# RFDesign.net
KiCad netlist of a schematic drawn in Altium Designer
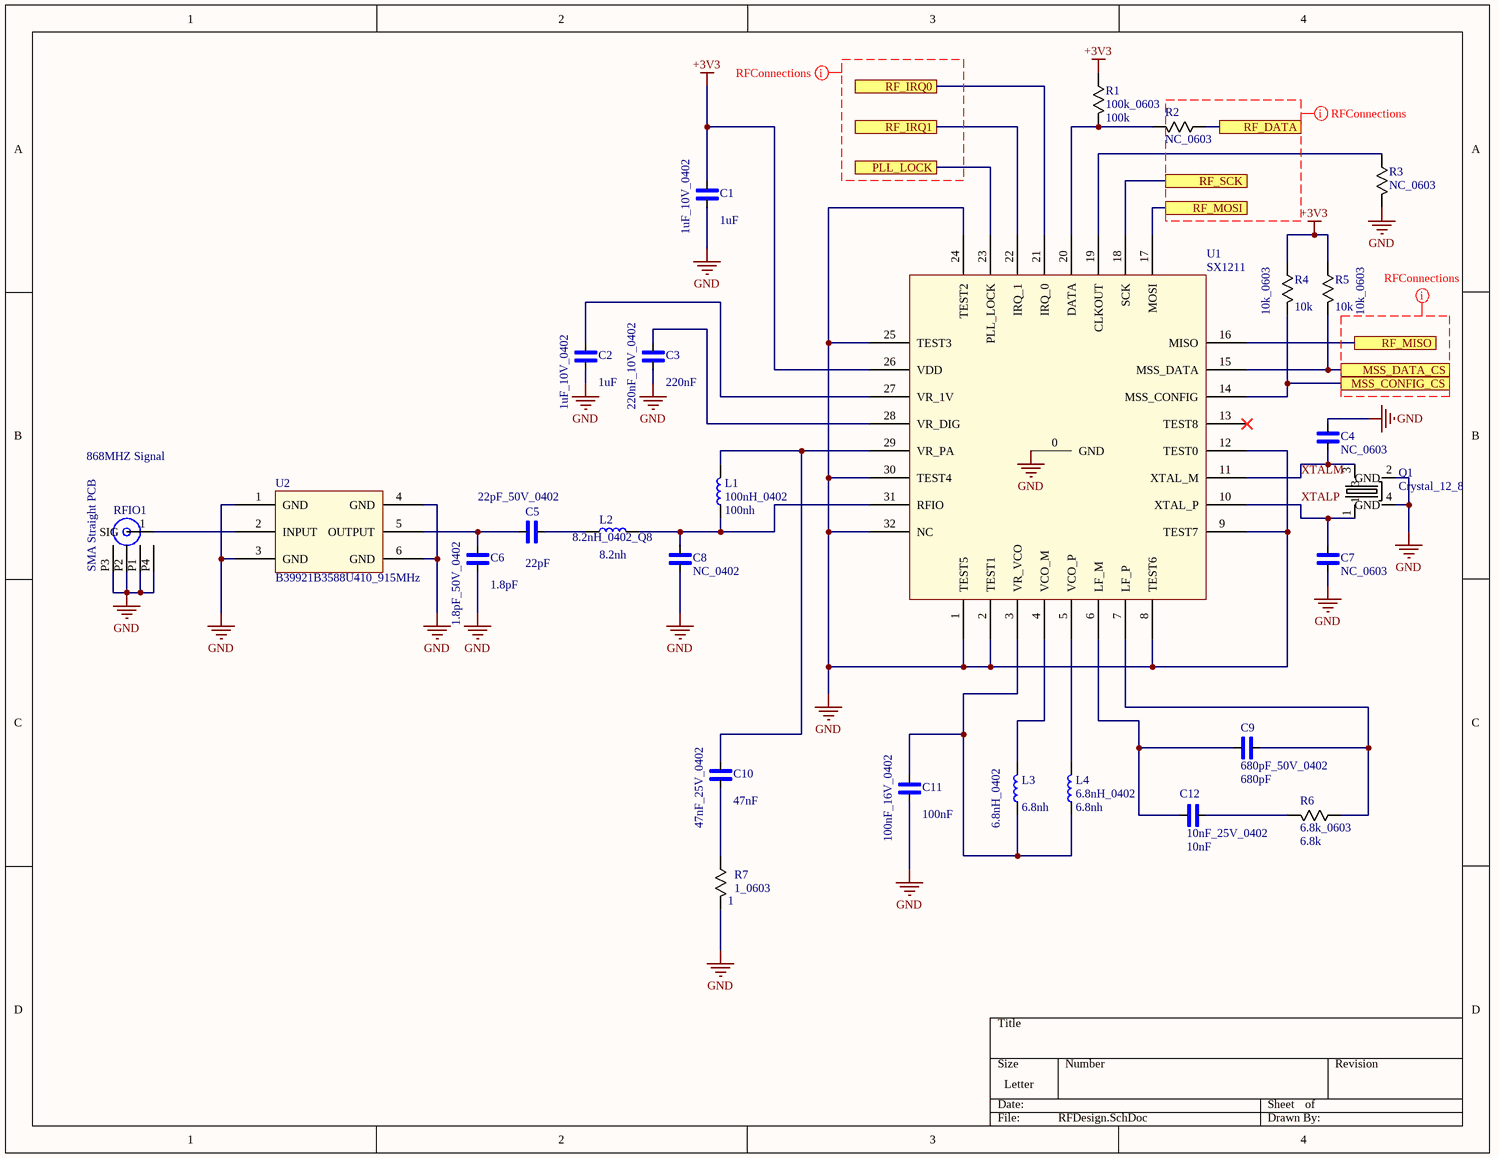
[diagram p0: RFDesign.SchDoc]

(export (version "E")
  (design (tool "Eeschema 10.0.6"))
  (components
    (comp (ref "C1")
      (value "1uF_10V_0402")
      (footprint "0402")
      (fields
        (field (name "MANUFACTURER") "Murata")
        (field (name "MANUFACTURER PART NUMBER") "GRM155R61A105KE15D")
        (field (name "TOLERANCE") "20%")
        (field (name "CAPACITANCE") "1uF")
      )
      (libsource (lib "Capacitors") (part "1uF_10V_0402"))
    )
    (comp (ref "C2")
      (value "1uF_10V_0402")
      (footprint "0402")
      (fields
        (field (name "MANUFACTURER") "Murata")
        (field (name "MANUFACTURER PART NUMBER") "GRM155R61A105KE15D")
        (field (name "TOLERANCE") "20%")
        (field (name "CAPACITANCE") "1uF")
      )
      (libsource (lib "Capacitors") (part "1uF_10V_0402"))
    )
    (comp (ref "C3")
      (value "220nF_10V_0402")
      (footprint "0402")
      (fields
        (field (name "MANUFACTURER") "Murata")
        (field (name "MANUFACTURER PART NUMBER") "GRM155R61A224KE19J")
        (field (name "TOLERANCE") "10%")
        (field (name "CAPACITANCE") "220nF")
      )
      (libsource (lib "Capacitors") (part "220nF_10V_0402"))
    )
    (comp (ref "C4") (value "NC_0603") (footprint "0603") (libsource (lib "Capacitors") (part "NC_0603")))
    (comp (ref "C5")
      (value "22pF_50V_0402")
      (footprint "0402")
      (fields
        (field (name "MANUFACTURER") "Murata")
        (field (name "MANUFACTURER PART NUMBER") "GRM1555C1H220JA01D")
        (field (name "TOLERANCE") "5%")
        (field (name "CAPACITANCE") "22pF")
      )
      (libsource (lib "Capacitors") (part "22pF_50V_0402"))
    )
    (comp (ref "C6")
      (value "1.8pF_50V_0402")
      (footprint "0402")
      (fields
        (field (name "MANUFACTURER") "Murata")
        (field (name "MANUFACTURER PART NUMBER") "GRM1555C1H1R8CA01D")
        (field (name "VOLTAGE") "50V")
        (field (name "CAPACITANCE") "1.8pF")
      )
      (libsource (lib "Capacitors") (part "1.8pF_50V_0402"))
    )
    (comp (ref "C7") (value "NC_0603") (footprint "0603") (libsource (lib "Capacitors") (part "NC_0603")))
    (comp (ref "C8") (value "NC_0402") (footprint "0402") (libsource (lib "Capacitors") (part "NC_0402")))
    (comp (ref "C9")
      (value "680pF_50V_0402")
      (footprint "0402")
      (fields
        (field (name "MANUFACTURER") "Murata")
        (field (name "MANUFACTURER PART NUMBER") "GRM1555C1H681JA01D")
        (field (name "TOLERANCE") "5%")
        (field (name "CAPACITANCE") "680pF")
      )
      (libsource (lib "Capacitors") (part "680pF_50V_0402"))
    )
    (comp (ref "C10")
      (value "47nF_25V_0402")
      (footprint "0402")
      (fields
        (field (name "MANUFACTURER") "Murata")
        (field (name "MANUFACTURER PART NUMBER") "GRM155R71E473KA88J")
        (field (name "TOLERANCE") "10%")
        (field (name "CAPACITANCE") "47nF")
      )
      (libsource (lib "Capacitors") (part "47nF_25V_0402"))
    )
    (comp (ref "C11")
      (value "100nF_16V_0402")
      (footprint "0402")
      (fields
        (field (name "MANUFACTURER") "Murata")
        (field (name "MANUFACTURER PART NUMBER") "GRM155-R7-1C-104K-A88-D")
        (field (name "TOLERANCE") "10%")
        (field (name "CAPACITANCE") "100nF")
      )
      (libsource (lib "Capacitors") (part "100nF_16V_0402"))
    )
    (comp (ref "C12")
      (value "10nF_25V_0402")
      (footprint "0402")
      (fields
        (field (name "MANUFACTURER") "Murata")
        (field (name "MANUFACTURER PART NUMBER") "GRM155R71E103KA01D")
        (field (name "TOLERANCE") "10%")
        (field (name "CAPACITANCE") "10nF")
      )
      (libsource (lib "Capacitors") (part "10nF_25V_0402"))
    )
    (comp (ref "L1")
      (value "100nH_0402")
      (footprint "0402")
      (fields
        (field (name "MANUFACTURER") "Murata")
        (field (name "MANUFACTURER PART NUMBER") "LQW15ANR10J00D")
        (field (name "TOLERANCE") "5%")
        (field (name "INDUCTANCE") "100nh")
      )
      (libsource (lib "Inductors") (part "100nH_0402"))
    )
    (comp (ref "L2")
      (value "8.2nH_0402_Q8")
      (footprint "0402")
      (fields
        (field (name "MANUFACTURER") "Murata")
        (field (name "MANUFACTURER PART NUMBER") "LQG15HS8N2J02D")
        (field (name "TOLERANCE") "5%")
        (field (name "INDUCTANCE") "8.2nh")
      )
      (libsource (lib "Inductors") (part "8.2nH_0402_Q8"))
    )
    (comp (ref "L3")
      (value "6.8nH_0402")
      (footprint "0402")
      (fields
        (field (name "MANUFACTURER") "Murata")
        (field (name "MANUFACTURER PART NUMBER") "LQW15AN6N8H00D")
        (field (name "TOLERANCE") "3%")
        (field (name "INDUCTANCE") "6.8nh")
      )
      (libsource (lib "Inductors") (part "6.8nH_0402"))
    )
    (comp (ref "L4")
      (value "6.8nH_0402")
      (footprint "0402")
      (fields
        (field (name "MANUFACTURER") "Murata")
        (field (name "MANUFACTURER PART NUMBER") "LQW15AN6N8H00D")
        (field (name "TOLERANCE") "3%")
        (field (name "INDUCTANCE") "6.8nh")
      )
      (libsource (lib "Inductors") (part "6.8nH_0402"))
    )
    (comp (ref "Q1")
      (value "Crystal_12_8")
      (footprint "4-SMD No Lead")
      (description "CRYSTAL 12.8000MHZ 10PF SMD")
      (fields (field (name "PART NO") "ABM3B-12.800MHZ-10-1-U-T"))
      (libsource (lib "Crystals") (part "Crystal_12_8"))
    )
    (comp (ref "R1")
      (value "100k_0603")
      (footprint "0603")
      (fields
        (field (name "MANUFACTURER") "Vishay")
        (field (name "MANUFACTURER PART NUMBER") "CRCW0603100KFKEA")
        (field (name "TOLERANCE") "1%")
        (field (name "RESISTANCE") "100k")
      )
      (libsource (lib "Resistors") (part "100k_0603"))
    )
    (comp (ref "R2") (value "NC_0603") (footprint "0603") (libsource (lib "Resistors") (part "NC_0603")))
    (comp (ref "R3") (value "NC_0603") (footprint "0603") (libsource (lib "Resistors") (part "NC_0603")))
    (comp (ref "R4")
      (value "10k_0603")
      (footprint "0603")
      (fields
        (field (name "MANUFACTURER") "Panasonic")
        (field (name "MANUFACTURER PART NUMBER") "ERJ-3EKF1002V")
        (field (name "TOLERANCE") "1%")
        (field (name "RESISTANCE") "10k")
      )
      (libsource (lib "Resistors") (part "10k_0603"))
    )
    (comp (ref "R5")
      (value "10k_0603")
      (footprint "0603")
      (fields
        (field (name "MANUFACTURER") "Panasonic")
        (field (name "MANUFACTURER PART NUMBER") "ERJ-3EKF1002V")
        (field (name "TOLERANCE") "1%")
        (field (name "RESISTANCE") "10k")
      )
      (libsource (lib "Resistors") (part "10k_0603"))
    )
    (comp (ref "R6")
      (value "6.8k_0603")
      (footprint "0603")
      (fields
        (field (name "MANUFACTURER") "Vishay")
        (field (name "MANUFACTURER PART NUMBER") "CRCW06036K80FKEA")
        (field (name "TOLERANCE") "1%")
        (field (name "RESISTANCE") "6.8k")
      )
      (libsource (lib "Resistors") (part "6.8k_0603"))
    )
    (comp (ref "R7")
      (value "1_0603")
      (footprint "0603")
      (fields
        (field (name "MANUFACTURER") "Vishay Dale")
        (field (name "MANUFACTURER PART NUMBER") "CRCW06031R00FKEA")
        (field (name "TOLERANCE") "1%")
        (field (name "RESISTANCE") "1")
      )
      (libsource (lib "Resistors") (part "1_0603"))
    )
    (comp (ref "RFIO1")
      (value "SMA Straight PCB")
      (footprint "SMA Straight PCB")
      (description "RF Connector SMA Straight PCB Jack Surface Mount 50 Ohm")
      (fields (field (name "PART NO") "132134-15"))
      (libsource (lib "Connectors") (part "SMA Straight PCB"))
    )
    (comp (ref "U1")
      (value "SX1211")
      (footprint "SX1211")
      (description "SX1211I084")
      (libsource (lib "RFICs") (part "SX1211"))
    )
    (comp (ref "U2")
      (value "B39921B3588U410_915MHz")
      (footprint "B39871B3715U410")
      (libsource (lib "Filters") (part "B39921B3588U410_915MHz"))
    )
  )
  (nets
    (net (code "1") (name "+3V3") (class "Default")
      (node (ref "C1") (pin "2") (pinfunction "2_2") (pintype "passive"))
      (node (ref "R1") (pin "2") (pinfunction "2_2") (pintype "passive"))
      (node (ref "R4") (pin "2") (pinfunction "2_2") (pintype "passive"))
      (node (ref "R5") (pin "2") (pinfunction "2_2") (pintype "passive"))
      (node (ref "U1") (pin "26") (pinfunction "VDD_26") (pintype "passive"))
    )
    (net (code "2") (name "/MSS_CONFIG_CS") (class "Default")
      (node (ref "R4") (pin "1") (pinfunction "1_1") (pintype "passive"))
      (node (ref "U1") (pin "14") (pinfunction "MSS_CONFIG_14") (pintype "passive"))
    )
    (net (code "3") (name "/MSS_DATA_CS") (class "Default")
      (node (ref "R5") (pin "1") (pinfunction "1_1") (pintype "passive"))
      (node (ref "U1") (pin "15") (pinfunction "MSS_DATA_15") (pintype "passive"))
    )
    (net (code "4") (name "/PLL_LOCK") (class "Default")
      (node (ref "U1") (pin "23") (pinfunction "PLL_LOCK_23") (pintype "passive"))
    )
    (net (code "5") (name "/RF_DATA") (class "Default")
      (node (ref "R2") (pin "2") (pinfunction "2_2") (pintype "passive"))
    )
    (net (code "6") (name "/RF_IRQ0") (class "Default")
      (node (ref "U1") (pin "21") (pinfunction "IRQ_0_21") (pintype "passive"))
    )
    (net (code "7") (name "/RF_IRQ1") (class "Default")
      (node (ref "U1") (pin "22") (pinfunction "IRQ_1_22") (pintype "passive"))
    )
    (net (code "8") (name "/RF_MISO") (class "Default")
      (node (ref "U1") (pin "16") (pinfunction "MISO_16") (pintype "passive"))
    )
    (net (code "9") (name "/RF_MOSI") (class "Default")
      (node (ref "U1") (pin "17") (pinfunction "MOSI_17") (pintype "passive"))
    )
    (net (code "10") (name "/RF_SCK") (class "Default")
      (node (ref "U1") (pin "18") (pinfunction "SCK_18") (pintype "passive"))
    )
    (net (code "11") (name "/XTALM") (class "Default")
      (node (ref "C4") (pin "1") (pinfunction "1_1") (pintype "passive"))
      (node (ref "Q1") (pin "3") (pinfunction "3_3") (pintype "passive"))
      (node (ref "U1") (pin "11") (pinfunction "XTAL_M_11") (pintype "passive"))
    )
    (net (code "12") (name "/XTALP") (class "Default")
      (node (ref "C7") (pin "2") (pinfunction "2_2") (pintype "passive"))
      (node (ref "Q1") (pin "1") (pinfunction "1_1") (pintype "passive"))
      (node (ref "U1") (pin "10") (pinfunction "XTAL_P_10") (pintype "passive"))
    )
    (net (code "13") (name "GND") (class "Default")
      (node (ref "C1") (pin "1") (pinfunction "1_1") (pintype "passive"))
      (node (ref "C11") (pin "1") (pinfunction "1_1") (pintype "passive"))
      (node (ref "C2") (pin "1") (pinfunction "1_1") (pintype "passive"))
      (node (ref "C3") (pin "1") (pinfunction "1_1") (pintype "passive"))
      (node (ref "C4") (pin "2") (pinfunction "2_2") (pintype "passive"))
      (node (ref "C6") (pin "1") (pinfunction "1_1") (pintype "passive"))
      (node (ref "C7") (pin "1") (pinfunction "1_1") (pintype "passive"))
      (node (ref "C8") (pin "1") (pinfunction "1_1") (pintype "passive"))
      (node (ref "Q1") (pin "2") (pinfunction "GND_2") (pintype "passive"))
      (node (ref "Q1") (pin "4") (pinfunction "GND_4") (pintype "passive"))
      (node (ref "R3") (pin "1") (pinfunction "1_1") (pintype "passive"))
      (node (ref "R7") (pin "1") (pinfunction "1_1") (pintype "passive"))
      (node (ref "RFIO1") (pin "P1") (pintype "passive"))
      (node (ref "RFIO1") (pin "P2") (pintype "passive"))
      (node (ref "RFIO1") (pin "P3") (pintype "passive"))
      (node (ref "RFIO1") (pin "P4") (pintype "passive"))
      (node (ref "U1") (pin "0") (pinfunction "GND_0") (pintype "passive"))
      (node (ref "U1") (pin "1") (pinfunction "TEST5_1") (pintype "passive"))
      (node (ref "U1") (pin "12") (pinfunction "TEST0_12") (pintype "passive"))
      (node (ref "U1") (pin "2") (pinfunction "TEST1_2") (pintype "passive"))
      (node (ref "U1") (pin "24") (pinfunction "TEST2_24") (pintype "passive"))
      (node (ref "U1") (pin "25") (pinfunction "TEST3_25") (pintype "passive"))
      (node (ref "U1") (pin "30") (pinfunction "TEST4_30") (pintype "passive"))
      (node (ref "U1") (pin "32") (pinfunction "NC_32") (pintype "passive"))
      (node (ref "U1") (pin "8") (pinfunction "TEST6_8") (pintype "passive"))
      (node (ref "U1") (pin "9") (pinfunction "TEST7_9") (pintype "passive"))
      (node (ref "U2") (pin "1") (pinfunction "GND_1") (pintype "passive"))
      (node (ref "U2") (pin "3") (pinfunction "GND_3") (pintype "passive"))
      (node (ref "U2") (pin "4") (pinfunction "GND_4") (pintype "passive"))
      (node (ref "U2") (pin "6") (pinfunction "GND_6") (pintype "passive"))
    )
    (net (code "14") (name "Net-(C5-Pad2)") (class "Default")
      (node (ref "C5") (pin "2") (pinfunction "2_2") (pintype "passive"))
      (node (ref "L2") (pin "1") (pinfunction "1_1") (pintype "passive"))
    )
    (net (code "15") (name "Net-(C10-Pad1)") (class "Default")
      (node (ref "C10") (pin "1") (pinfunction "1_1") (pintype "passive"))
      (node (ref "R7") (pin "2") (pinfunction "2_2") (pintype "passive"))
    )
    (net (code "16") (name "Net-(C12-Pad2)") (class "Default")
      (node (ref "C12") (pin "2") (pinfunction "2_2") (pintype "passive"))
      (node (ref "R6") (pin "1") (pinfunction "1_1") (pintype "passive"))
    )
    (net (code "17") (name "Net-(RFIO1-SIG)") (class "Default")
      (node (ref "RFIO1") (pin "1") (pinfunction "SIG_1") (pintype "passive"))
      (node (ref "U2") (pin "2") (pinfunction "INPUT_2") (pintype "passive"))
    )
    (net (code "18") (name "Net-(U1-CLKOUT)") (class "Default")
      (node (ref "R3") (pin "2") (pinfunction "2_2") (pintype "passive"))
      (node (ref "U1") (pin "19") (pinfunction "CLKOUT_19") (pintype "passive"))
    )
    (net (code "19") (name "Net-(U1-DATA)") (class "Default")
      (node (ref "R1") (pin "1") (pinfunction "1_1") (pintype "passive"))
      (node (ref "R2") (pin "1") (pinfunction "1_1") (pintype "passive"))
      (node (ref "U1") (pin "20") (pinfunction "DATA_20") (pintype "passive"))
    )
    (net (code "20") (name "Net-(U1-LF_M)") (class "Default")
      (node (ref "C12") (pin "1") (pinfunction "1_1") (pintype "passive"))
      (node (ref "C9") (pin "1") (pinfunction "1_1") (pintype "passive"))
      (node (ref "U1") (pin "6") (pinfunction "LF_M_6") (pintype "passive"))
    )
    (net (code "21") (name "Net-(U1-LF_P)") (class "Default")
      (node (ref "C9") (pin "2") (pinfunction "2_2") (pintype "passive"))
      (node (ref "R6") (pin "2") (pinfunction "2_2") (pintype "passive"))
      (node (ref "U1") (pin "7") (pinfunction "LF_P_7") (pintype "passive"))
    )
    (net (code "22") (name "Net-(U1-RFIO)") (class "Default")
      (node (ref "C8") (pin "2") (pinfunction "2_2") (pintype "passive"))
      (node (ref "L1") (pin "1") (pinfunction "1_1") (pintype "passive"))
      (node (ref "L2") (pin "2") (pinfunction "2_2") (pintype "passive"))
      (node (ref "U1") (pin "31") (pinfunction "RFIO_31") (pintype "passive"))
    )
    (net (code "23") (name "Net-(U1-VCO_M)") (class "Default")
      (node (ref "L3") (pin "2") (pinfunction "2_2") (pintype "passive"))
      (node (ref "U1") (pin "4") (pinfunction "VCO_M_4") (pintype "passive"))
    )
    (net (code "24") (name "Net-(U1-VCO_P)") (class "Default")
      (node (ref "L4") (pin "2") (pinfunction "2_2") (pintype "passive"))
      (node (ref "U1") (pin "5") (pinfunction "VCO_P_5") (pintype "passive"))
    )
    (net (code "25") (name "Net-(U1-VR_1V)") (class "Default")
      (node (ref "C2") (pin "2") (pinfunction "2_2") (pintype "passive"))
      (node (ref "U1") (pin "27") (pinfunction "VR_1V_27") (pintype "passive"))
    )
    (net (code "26") (name "Net-(U1-VR_DIG)") (class "Default")
      (node (ref "C3") (pin "2") (pinfunction "2_2") (pintype "passive"))
      (node (ref "U1") (pin "28") (pinfunction "VR_DIG_28") (pintype "passive"))
    )
    (net (code "27") (name "Net-(U1-VR_PA)") (class "Default")
      (node (ref "C10") (pin "2") (pinfunction "2_2") (pintype "passive"))
      (node (ref "L1") (pin "2") (pinfunction "2_2") (pintype "passive"))
      (node (ref "U1") (pin "29") (pinfunction "VR_PA_29") (pintype "passive"))
    )
    (net (code "28") (name "Net-(U1-VR_VCO)") (class "Default")
      (node (ref "C11") (pin "2") (pinfunction "2_2") (pintype "passive"))
      (node (ref "L3") (pin "1") (pinfunction "1_1") (pintype "passive"))
      (node (ref "L4") (pin "1") (pinfunction "1_1") (pintype "passive"))
      (node (ref "U1") (pin "3") (pinfunction "VR_VCO_3") (pintype "passive"))
    )
    (net (code "29") (name "Net-(U2-OUTPUT)") (class "Default")
      (node (ref "C5") (pin "1") (pinfunction "1_1") (pintype "passive"))
      (node (ref "C6") (pin "2") (pinfunction "2_2") (pintype "passive"))
      (node (ref "U2") (pin "5") (pinfunction "OUTPUT_5") (pintype "passive"))
    )
    (net (code "30") (name "unconnected-(U1-TEST8-Pad13)") (class "Default")
      (node (ref "U1") (pin "13") (pinfunction "TEST8_13") (pintype "passive+no_connect"))
    )
  )
)
